# asa.net
KiCad netlist of a schematic drawn in EAGLE
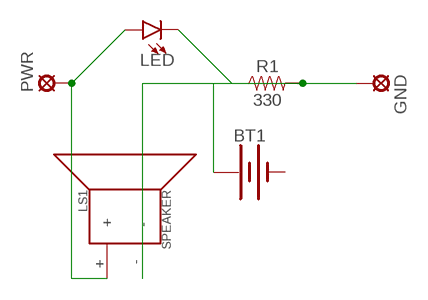
[diagram p0: schematic, sheet 1]

(export (version "E")
  (design (tool "Eeschema 10.0.6"))
  (components
    (comp (ref "BT1")
      (value "BATTERY-12MM_PTH")
      (footprint "eagle-import:BATTCON_12MM_PTH")
      (libsource (lib "eagle-import") (part "BATTERY-12MM_PTH"))
    )
    (comp (ref "GND")
      (value "LSP11")
      (footprint "eagle-import:LSP11")
      (libsource (lib "eagle-import") (part "LSP11"))
    )
    (comp (ref "LED")
      (value "LED3MM")
      (footprint "eagle-import:LED_3MM")
      (libsource (lib "eagle-import") (part "LED3MM"))
    )
    (comp (ref "LS1")
      (value "SPEAKER")
      (footprint "eagle-import:PCB_MOUNT_SPEAKER")
      (libsource (lib "eagle-import") (part "SPEAKER"))
    )
    (comp (ref "PWR")
      (value "LSP11")
      (footprint "eagle-import:LSP11")
      (libsource (lib "eagle-import") (part "LSP11"))
    )
    (comp (ref "R1")
      (value "330")
      (footprint "eagle-import:AXIAL-0.3")
      (libsource (lib "eagle-import") (part "RESISTORAXIAL-0.3"))
    )
  )
  (nets
    (net (code "1") (name "/-") (class "Default")
      (node (ref "BT1") (pin "GND") (pinfunction "-_GND") (pintype "power_in"))
    )
    (net (code "2") (name "Net-(BT1-+)") (class "Default")
      (node (ref "BT1") (pin "VCC@1") (pinfunction "+_VCC@1") (pintype "power_in"))
      (node (ref "GND") (pin "MP") (pinfunction "MP_MP") (pintype "passive"))
      (node (ref "LS1") (pin "-") (pinfunction "-_-") (pintype "bidirectional"))
      (node (ref "R1") (pin "P$2") (pinfunction "2_P$2") (pintype "passive"))
    )
    (net (code "3") (name "Net-(LED-C)") (class "Default")
      (node (ref "LED") (pin "K") (pinfunction "C_K") (pintype "passive"))
      (node (ref "R1") (pin "P$1") (pinfunction "1_P$1") (pintype "passive"))
    )
    (net (code "4") (name "Net-(LED-PadA)") (class "Default")
      (node (ref "LED") (pin "A") (pinfunction "A_A") (pintype "passive"))
      (node (ref "LS1") (pin "+") (pinfunction "+_+") (pintype "bidirectional"))
      (node (ref "PWR") (pin "MP") (pinfunction "MP_MP") (pintype "passive"))
    )
  )
)
